# PCB_power_glider_v13.net
KiCad netlist of a schematic drawn in EAGLE
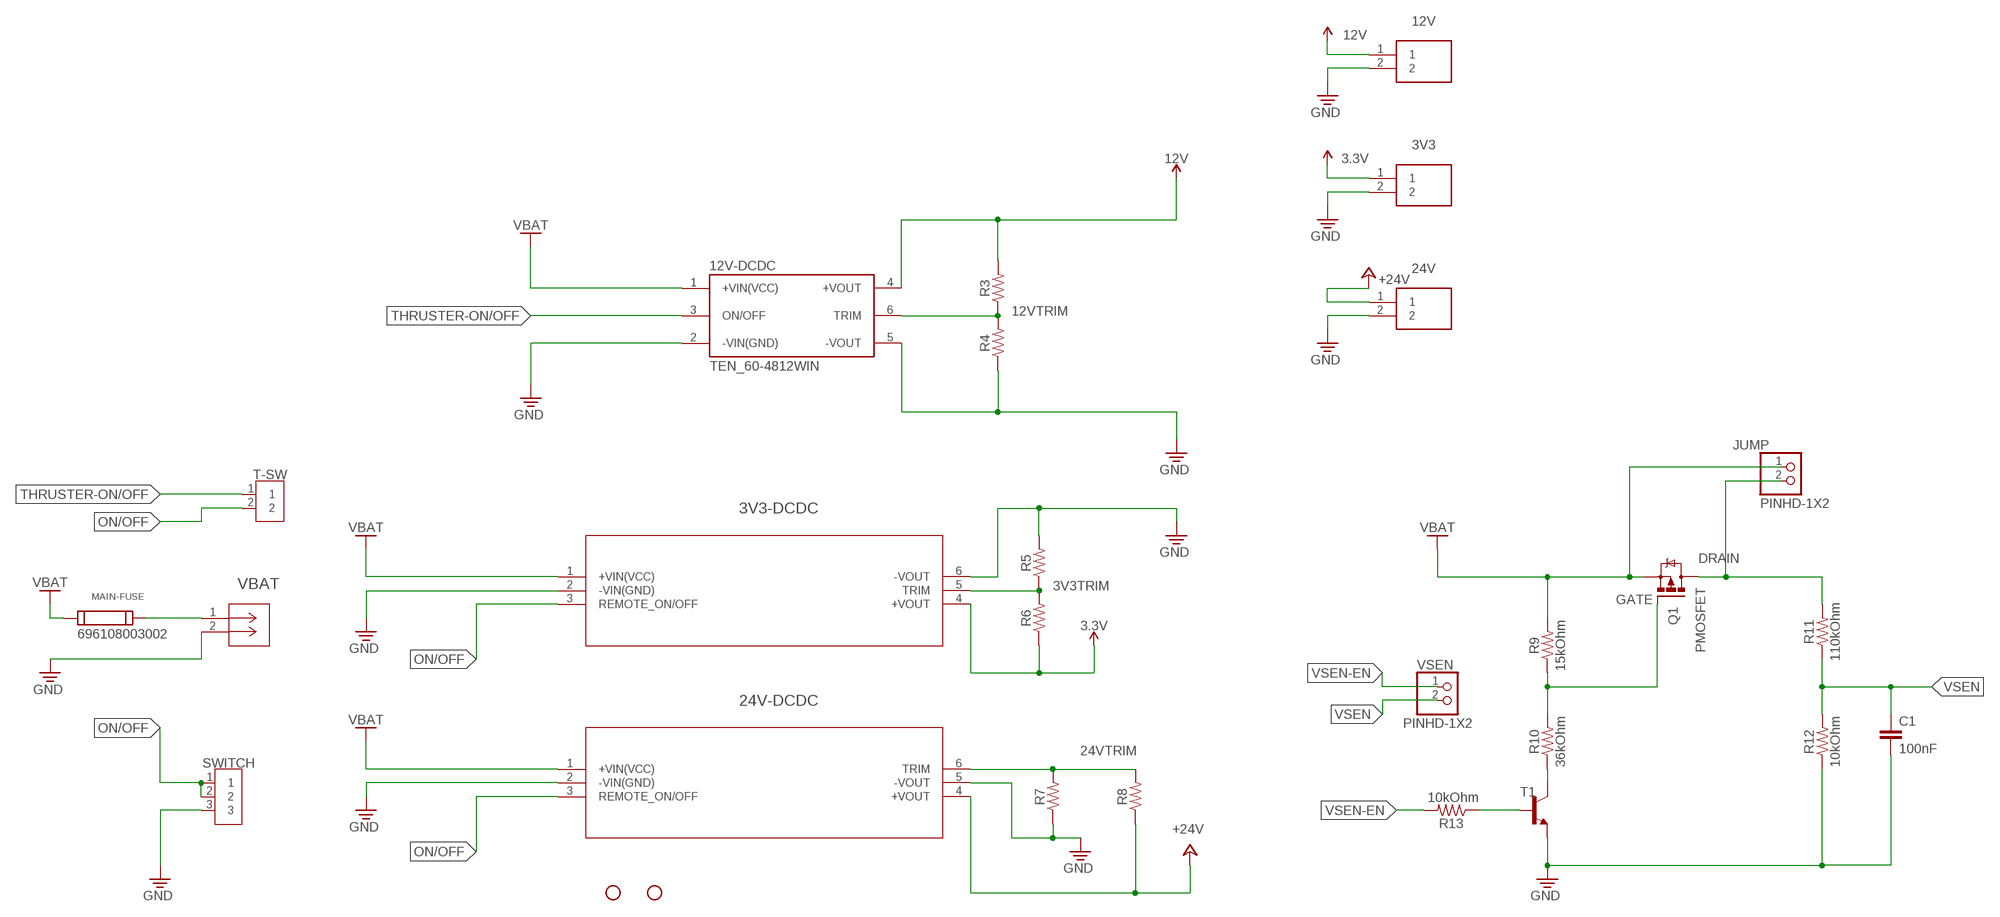
[diagram p0: schematic, sheet 1]

(export (version "E")
  (design (tool "Eeschema 10.0.6"))
  (components
    (comp (ref "3V3")
      (value "CTBP0508_2")
      (footprint "eagle-import:CTBP05082")
      (fields (field (name "MANUFACTURER_PART_NUMBER") "CTBP0508/2"))
      (libsource (lib "eagle-import") (part "CTBP0508_2"))
    )
    (comp (ref "3V3-DCDC")
      (value "THN_20-4810WIRTHN_20WIR_SINGLE_TRP")
      (footprint "eagle-import:THN_20WIR_SINGLE_TRP")
      (fields
        (field (name "MANUFACTURER_PART_NUMBER") "THN 20-4810WIR")
        (field (name "COPYRIGHT") "Copyright (C) 2024 Ultra Librarian. All rights reserved.")
      )
      (libsource (lib "eagle-import") (part "THN_20-4810WIRTHN_20WIR_SINGLE_TRP"))
    )
    (comp (ref "12V")
      (value "CTBP0508_2")
      (footprint "eagle-import:CTBP05082")
      (fields (field (name "MANUFACTURER_PART_NUMBER") "CTBP0508/2"))
      (libsource (lib "eagle-import") (part "CTBP0508_2"))
    )
    (comp (ref "12V-DCDC")
      (value "TEN_60-4812WIN")
      (footprint "eagle-import:CONV_TEN_60-4812WIN")
      (fields (field (name "MF") "Traco Power") (field (name "MP") "TEN 60-4812WIN"))
      (libsource (lib "eagle-import") (part "TEN_60-4812WIN"))
    )
    (comp (ref "24V")
      (value "CTBP0508_2")
      (footprint "eagle-import:CTBP05082")
      (fields (field (name "MANUFACTURER_PART_NUMBER") "CTBP0508/2"))
      (libsource (lib "eagle-import") (part "CTBP0508_2"))
    )
    (comp (ref "24V-DCDC")
      (value "TEN_60-4815WINTEN_60WIN_TRP")
      (footprint "eagle-import:TEN_60WIN_TRP")
      (fields
        (field (name "MANUFACTURER_PART_NUMBER") "TEN 60-4815WIN")
        (field (name "COPYRIGHT") "Copyright (C) 2024 Ultra Librarian. All rights reserved.")
      )
      (libsource (lib "eagle-import") (part "TEN_60-4815WINTEN_60WIN_TRP"))
    )
    (comp (ref "C1")
      (value "100nF")
      (footprint "eagle-import:0603")
      (libsource (lib "eagle-import") (part "CAP-0603"))
    )
    (comp (ref "H1")
      (value "STAND-OFFTIGHT")
      (footprint "eagle-import:STAND-OFF-TIGHT")
      (libsource (lib "eagle-import") (part "STAND-OFFTIGHT"))
    )
    (comp (ref "H4")
      (value "STAND-OFFTIGHT")
      (footprint "eagle-import:STAND-OFF-TIGHT")
      (libsource (lib "eagle-import") (part "STAND-OFFTIGHT"))
    )
    (comp (ref "JUMP")
      (value "PINHD-1X2")
      (footprint "eagle-import:1X02")
      (fields (field (name "MANUFACTURER") "Generic"))
      (libsource (lib "eagle-import") (part "PINHD-1X2"))
    )
    (comp (ref "MAIN-FUSE")
      (value "696108003002")
      (footprint "eagle-import:696108003002")
      (libsource (lib "eagle-import") (part "696108003002"))
    )
    (comp (ref "Q1")
      (value "PMOSFET")
      (footprint "eagle-import:SOT23")
      (libsource (lib "eagle-import") (part "PMOSFETSOT23-GSD_"))
    )
    (comp (ref "R3")
      (value "RESISTOR0603")
      (footprint "eagle-import:0603")
      (libsource (lib "eagle-import") (part "RESISTOR0603"))
    )
    (comp (ref "R4")
      (value "RESISTOR0603")
      (footprint "eagle-import:0603")
      (libsource (lib "eagle-import") (part "RESISTOR0603"))
    )
    (comp (ref "R5")
      (value "RESISTOR0603")
      (footprint "eagle-import:0603")
      (libsource (lib "eagle-import") (part "RESISTOR0603"))
    )
    (comp (ref "R6")
      (value "RESISTOR0603")
      (footprint "eagle-import:0603")
      (libsource (lib "eagle-import") (part "RESISTOR0603"))
    )
    (comp (ref "R7")
      (value "RESISTOR0603")
      (footprint "eagle-import:0603")
      (libsource (lib "eagle-import") (part "RESISTOR0603"))
    )
    (comp (ref "R8")
      (value "RESISTOR0603")
      (footprint "eagle-import:0603")
      (libsource (lib "eagle-import") (part "RESISTOR0603"))
    )
    (comp (ref "R9")
      (value "15kOhm")
      (footprint "eagle-import:0603")
      (libsource (lib "eagle-import") (part "RESISTOR0603"))
    )
    (comp (ref "R10")
      (value "36kOhm")
      (footprint "eagle-import:0603")
      (libsource (lib "eagle-import") (part "RESISTOR0603"))
    )
    (comp (ref "R11")
      (value "110kOhm")
      (footprint "eagle-import:0603")
      (libsource (lib "eagle-import") (part "RESISTOR0603"))
    )
    (comp (ref "R12")
      (value "10kOhm")
      (footprint "eagle-import:0603")
      (libsource (lib "eagle-import") (part "RESISTOR0603"))
    )
    (comp (ref "R13")
      (value "10kOhm")
      (footprint "eagle-import:0603")
      (libsource (lib "eagle-import") (part "RESISTOR0603"))
    )
    (comp (ref "SWITCH")
      (value "2828XX-3282834-3")
      (footprint "eagle-import:TERMBLK_254-3N")
      (fields (field (name "MANUFACTURER") "TE Connectivity AMP Connectors") (field (name "MPN") "282834-3"))
      (libsource (lib "eagle-import") (part "2828XX-3282834-3"))
    )
    (comp (ref "T-SW")
      (value "2828XX-2282834-2")
      (footprint "eagle-import:TERMBLK_254-2N")
      (fields (field (name "MANUFACTURER") "TE Connectivity AMP Connectors") (field (name "MPN") "282834-2 "))
      (libsource (lib "eagle-import") (part "2828XX-2282834-2"))
    )
    (comp (ref "T1")
      (value "-NPN-SOT23-EBC")
      (footprint "eagle-import:SOT23-EBC")
      (libsource (lib "eagle-import") (part "-NPN-SOT23-EBC"))
    )
    (comp (ref "VBAT")
      (value "NC6-P107-02CONN2_1437664-4_TEC")
      (footprint "eagle-import:CONN2_1437664-4_TEC")
      (fields
        (field (name "MANUFACTURER_PART_NUMBER") "NC6-P107-02")
        (field (name "COPYRIGHT") "Copyright (C) 2024 Ultra Librarian. All rights reserved.")
      )
      (libsource (lib "eagle-import") (part "NC6-P107-02CONN2_1437664-4_TEC"))
    )
    (comp (ref "VSEN")
      (value "PINHD-1X2")
      (footprint "eagle-import:1X02")
      (fields (field (name "MANUFACTURER") "Generic"))
      (libsource (lib "eagle-import") (part "PINHD-1X2"))
    )
  )
  (nets
    (net (code "1") (name "+24V") (class "Default")
      (node (ref "24V") (pin "1") (pinfunction "1_1") (pintype "bidirectional"))
      (node (ref "24V-DCDC") (pin "4") (pinfunction "+VOUT_4") (pintype "output"))
      (node (ref "R8") (pin "1") (pinfunction "1_1") (pintype "passive"))
    )
    (net (code "2") (name "/3V3TRIM") (class "Default")
      (node (ref "3V3-DCDC") (pin "5") (pinfunction "TRIM_5") (pintype "passive"))
      (node (ref "R5") (pin "1") (pinfunction "1_1") (pintype "passive"))
      (node (ref "R6") (pin "2") (pinfunction "2_2") (pintype "passive"))
    )
    (net (code "3") (name "/12VTRIM") (class "Default")
      (node (ref "12V-DCDC") (pin "6") (pinfunction "TRIM_6") (pintype "passive"))
      (node (ref "R3") (pin "1") (pinfunction "1_1") (pintype "passive"))
      (node (ref "R4") (pin "2") (pinfunction "2_2") (pintype "passive"))
    )
    (net (code "4") (name "/24VTRIM") (class "Default")
      (node (ref "24V-DCDC") (pin "6") (pinfunction "TRIM_6") (pintype "passive"))
      (node (ref "R7") (pin "2") (pinfunction "2_2") (pintype "passive"))
      (node (ref "R8") (pin "2") (pinfunction "2_2") (pintype "passive"))
    )
    (net (code "5") (name "/DRAIN") (class "Default")
      (node (ref "JUMP") (pin "2") (pinfunction "2_2") (pintype "passive"))
      (node (ref "Q1") (pin "3") (pinfunction "D_3") (pintype "passive"))
      (node (ref "R11") (pin "2") (pinfunction "2_2") (pintype "passive"))
    )
    (net (code "6") (name "/GATE") (class "Default")
      (node (ref "Q1") (pin "1") (pinfunction "G_1") (pintype "passive"))
      (node (ref "R10") (pin "2") (pinfunction "2_2") (pintype "passive"))
      (node (ref "R9") (pin "1") (pinfunction "1_1") (pintype "passive"))
    )
    (net (code "7") (name "3.3V") (class "Default")
      (node (ref "3V3") (pin "1") (pinfunction "1_1") (pintype "bidirectional"))
      (node (ref "3V3-DCDC") (pin "4") (pinfunction "+VOUT_4") (pintype "power_in"))
      (node (ref "R6") (pin "1") (pinfunction "1_1") (pintype "passive"))
    )
    (net (code "8") (name "12V") (class "Default")
      (node (ref "12V") (pin "1") (pinfunction "1_1") (pintype "bidirectional"))
      (node (ref "12V-DCDC") (pin "4") (pinfunction "+VOUT_4") (pintype "output"))
      (node (ref "R3") (pin "2") (pinfunction "2_2") (pintype "passive"))
    )
    (net (code "9") (name "GND") (class "Default")
      (node (ref "12V") (pin "2") (pinfunction "2_2") (pintype "bidirectional"))
      (node (ref "12V-DCDC") (pin "2") (pinfunction "-VIN(GND)_2") (pintype "input"))
      (node (ref "12V-DCDC") (pin "5") (pinfunction "-VOUT_5") (pintype "output"))
      (node (ref "24V") (pin "2") (pinfunction "2_2") (pintype "bidirectional"))
      (node (ref "24V-DCDC") (pin "2") (pinfunction "-VIN(GND)_2") (pintype "power_in"))
      (node (ref "24V-DCDC") (pin "5") (pinfunction "-VOUT_5") (pintype "output"))
      (node (ref "3V3") (pin "2") (pinfunction "2_2") (pintype "bidirectional"))
      (node (ref "3V3-DCDC") (pin "2") (pinfunction "-VIN(GND)_2") (pintype "passive"))
      (node (ref "3V3-DCDC") (pin "6") (pinfunction "-VOUT_6") (pintype "power_in"))
      (node (ref "C1") (pin "2") (pinfunction "2_2") (pintype "passive"))
      (node (ref "R12") (pin "1") (pinfunction "1_1") (pintype "passive"))
      (node (ref "R4") (pin "1") (pinfunction "1_1") (pintype "passive"))
      (node (ref "R5") (pin "2") (pinfunction "2_2") (pintype "passive"))
      (node (ref "R7") (pin "1") (pinfunction "1_1") (pintype "passive"))
      (node (ref "SWITCH") (pin "3") (pinfunction "3_3") (pintype "bidirectional"))
      (node (ref "T1") (pin "E") (pinfunction "E_E") (pintype "passive"))
      (node (ref "VBAT") (pin "2") (pinfunction "2_2") (pintype "passive"))
    )
    (net (code "10") (name "Net-(MAIN-FUSE-Pad2)") (class "Default")
      (node (ref "MAIN-FUSE") (pin "2") (pinfunction "2_2") (pintype "passive"))
      (node (ref "VBAT") (pin "1") (pinfunction "1_1") (pintype "passive"))
    )
    (net (code "11") (name "Net-(R10-Pad1)") (class "Default")
      (node (ref "R10") (pin "1") (pinfunction "1_1") (pintype "passive"))
      (node (ref "T1") (pin "C") (pinfunction "C_C") (pintype "passive"))
    )
    (net (code "12") (name "Net-(R13-Pad1)") (class "Default")
      (node (ref "R13") (pin "1") (pinfunction "1_1") (pintype "passive"))
      (node (ref "T1") (pin "B") (pinfunction "B_B") (pintype "passive"))
    )
    (net (code "13") (name "ON{slash}OFF") (class "Default")
      (node (ref "24V-DCDC") (pin "3") (pinfunction "REMOTE_ON/OFF_3") (pintype "passive"))
      (node (ref "3V3-DCDC") (pin "3") (pinfunction "REMOTE_ON/OFF_3") (pintype "passive"))
      (node (ref "SWITCH") (pin "1") (pinfunction "1_1") (pintype "bidirectional"))
      (node (ref "SWITCH") (pin "2") (pinfunction "2_2") (pintype "bidirectional"))
      (node (ref "T-SW") (pin "2") (pinfunction "2_2") (pintype "bidirectional"))
    )
    (net (code "14") (name "THRUSTER-ON{slash}OFF") (class "Default")
      (node (ref "12V-DCDC") (pin "3") (pinfunction "ON/OFF_3") (pintype "input"))
      (node (ref "T-SW") (pin "1") (pinfunction "1_1") (pintype "bidirectional"))
    )
    (net (code "15") (name "VBAT") (class "Default")
      (node (ref "12V-DCDC") (pin "1") (pinfunction "+VIN(VCC)_1") (pintype "input"))
      (node (ref "24V-DCDC") (pin "1") (pinfunction "+VIN(VCC)_1") (pintype "power_in"))
      (node (ref "3V3-DCDC") (pin "1") (pinfunction "+VIN(VCC)_1") (pintype "power_in"))
      (node (ref "JUMP") (pin "1") (pinfunction "1_1") (pintype "passive"))
      (node (ref "MAIN-FUSE") (pin "1") (pinfunction "1_1") (pintype "passive"))
      (node (ref "Q1") (pin "2") (pinfunction "S_2") (pintype "passive"))
      (node (ref "R9") (pin "2") (pinfunction "2_2") (pintype "passive"))
    )
    (net (code "16") (name "VSEN") (class "Default")
      (node (ref "C1") (pin "1") (pinfunction "1_1") (pintype "passive"))
      (node (ref "R11") (pin "1") (pinfunction "1_1") (pintype "passive"))
      (node (ref "R12") (pin "2") (pinfunction "2_2") (pintype "passive"))
      (node (ref "VSEN") (pin "2") (pinfunction "2_2") (pintype "passive"))
    )
    (net (code "17") (name "VSEN-EN") (class "Default")
      (node (ref "R13") (pin "2") (pinfunction "2_2") (pintype "passive"))
      (node (ref "VSEN") (pin "1") (pinfunction "1_1") (pintype "passive"))
    )
  )
)
